# Brake.net
KiCad netlist of a schematic drawn in EAGLE
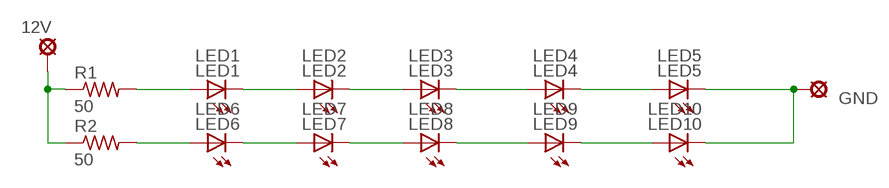
[diagram p0: schematic, sheet 1]

(export (version "E")
  (design (tool "Eeschema 10.0.6"))
  (components
    (comp (ref "12V")
      (value "LSP13")
      (footprint "eagle-import:LSP13")
      (libsource (lib "eagle-import") (part "LSP13"))
    )
    (comp (ref "GND")
      (value "LSP13")
      (footprint "eagle-import:LSP13")
      (libsource (lib "eagle-import") (part "LSP13"))
    )
    (comp (ref "LED1")
      (value "LED1")
      (footprint "eagle-import:CP41B")
      (libsource (lib "eagle-import") (part "LED-2AC-CP41B-WES"))
    )
    (comp (ref "LED2")
      (value "LED2")
      (footprint "eagle-import:CP41B")
      (libsource (lib "eagle-import") (part "LED-2AC-CP41B-WES"))
    )
    (comp (ref "LED3")
      (value "LED3")
      (footprint "eagle-import:CP41B")
      (libsource (lib "eagle-import") (part "LED-2AC-CP41B-WES"))
    )
    (comp (ref "LED4")
      (value "LED4")
      (footprint "eagle-import:CP41B")
      (libsource (lib "eagle-import") (part "LED-2AC-CP41B-WES"))
    )
    (comp (ref "LED5")
      (value "LED5")
      (footprint "eagle-import:CP41B")
      (libsource (lib "eagle-import") (part "LED-2AC-CP41B-WES"))
    )
    (comp (ref "LED6")
      (value "LED6")
      (footprint "eagle-import:CP41B")
      (libsource (lib "eagle-import") (part "LED-2AC-CP41B-WES"))
    )
    (comp (ref "LED7")
      (value "LED7")
      (footprint "eagle-import:CP41B")
      (libsource (lib "eagle-import") (part "LED-2AC-CP41B-WES"))
    )
    (comp (ref "LED8")
      (value "LED8")
      (footprint "eagle-import:CP41B")
      (libsource (lib "eagle-import") (part "LED-2AC-CP41B-WES"))
    )
    (comp (ref "LED9")
      (value "LED9")
      (footprint "eagle-import:CP41B")
      (libsource (lib "eagle-import") (part "LED-2AC-CP41B-WES"))
    )
    (comp (ref "LED10")
      (value "LED10")
      (footprint "eagle-import:CP41B")
      (libsource (lib "eagle-import") (part "LED-2AC-CP41B-WES"))
    )
    (comp (ref "R1")
      (value "50")
      (footprint "eagle-import:R1206")
      (libsource (lib "eagle-import") (part "R-US_R1206"))
    )
    (comp (ref "R2")
      (value "50")
      (footprint "eagle-import:R1206")
      (libsource (lib "eagle-import") (part "R-US_R1206"))
    )
  )
  (nets
    (net (code "1") (name "Net-(12V-PadMP)") (class "Default")
      (node (ref "12V") (pin "MP") (pinfunction "MP_MP") (pintype "passive"))
      (node (ref "R1") (pin "1") (pinfunction "1_1") (pintype "passive"))
      (node (ref "R2") (pin "1") (pinfunction "1_1") (pintype "passive"))
    )
    (net (code "2") (name "Net-(GND-PadMP)") (class "Default")
      (node (ref "GND") (pin "MP") (pinfunction "MP_MP") (pintype "passive"))
      (node (ref "LED10") (pin "1") (pinfunction "C_1") (pintype "passive"))
      (node (ref "LED10") (pin "4") (pinfunction "C_4") (pintype "passive"))
      (node (ref "LED5") (pin "1") (pinfunction "C_1") (pintype "passive"))
      (node (ref "LED5") (pin "4") (pinfunction "C_4") (pintype "passive"))
    )
    (net (code "3") (name "Net-(LED1-A-Pad2)") (class "Default")
      (node (ref "LED1") (pin "2") (pinfunction "A_2") (pintype "passive"))
      (node (ref "LED1") (pin "3") (pinfunction "A_3") (pintype "passive"))
      (node (ref "R1") (pin "2") (pinfunction "2_2") (pintype "passive"))
    )
    (net (code "4") (name "Net-(LED1-C-Pad1)") (class "Default")
      (node (ref "LED1") (pin "1") (pinfunction "C_1") (pintype "passive"))
      (node (ref "LED1") (pin "4") (pinfunction "C_4") (pintype "passive"))
      (node (ref "LED2") (pin "2") (pinfunction "A_2") (pintype "passive"))
      (node (ref "LED2") (pin "3") (pinfunction "A_3") (pintype "passive"))
    )
    (net (code "5") (name "Net-(LED2-C-Pad1)") (class "Default")
      (node (ref "LED2") (pin "1") (pinfunction "C_1") (pintype "passive"))
      (node (ref "LED2") (pin "4") (pinfunction "C_4") (pintype "passive"))
      (node (ref "LED3") (pin "2") (pinfunction "A_2") (pintype "passive"))
      (node (ref "LED3") (pin "3") (pinfunction "A_3") (pintype "passive"))
    )
    (net (code "6") (name "Net-(LED3-C-Pad1)") (class "Default")
      (node (ref "LED3") (pin "1") (pinfunction "C_1") (pintype "passive"))
      (node (ref "LED3") (pin "4") (pinfunction "C_4") (pintype "passive"))
      (node (ref "LED4") (pin "2") (pinfunction "A_2") (pintype "passive"))
      (node (ref "LED4") (pin "3") (pinfunction "A_3") (pintype "passive"))
    )
    (net (code "7") (name "Net-(LED4-C-Pad1)") (class "Default")
      (node (ref "LED4") (pin "1") (pinfunction "C_1") (pintype "passive"))
      (node (ref "LED4") (pin "4") (pinfunction "C_4") (pintype "passive"))
      (node (ref "LED5") (pin "2") (pinfunction "A_2") (pintype "passive"))
      (node (ref "LED5") (pin "3") (pinfunction "A_3") (pintype "passive"))
    )
    (net (code "8") (name "Net-(LED6-A-Pad2)") (class "Default")
      (node (ref "LED6") (pin "2") (pinfunction "A_2") (pintype "passive"))
      (node (ref "LED6") (pin "3") (pinfunction "A_3") (pintype "passive"))
      (node (ref "R2") (pin "2") (pinfunction "2_2") (pintype "passive"))
    )
    (net (code "9") (name "Net-(LED6-C-Pad1)") (class "Default")
      (node (ref "LED6") (pin "1") (pinfunction "C_1") (pintype "passive"))
      (node (ref "LED6") (pin "4") (pinfunction "C_4") (pintype "passive"))
      (node (ref "LED7") (pin "2") (pinfunction "A_2") (pintype "passive"))
      (node (ref "LED7") (pin "3") (pinfunction "A_3") (pintype "passive"))
    )
    (net (code "10") (name "Net-(LED7-C-Pad1)") (class "Default")
      (node (ref "LED7") (pin "1") (pinfunction "C_1") (pintype "passive"))
      (node (ref "LED7") (pin "4") (pinfunction "C_4") (pintype "passive"))
      (node (ref "LED8") (pin "2") (pinfunction "A_2") (pintype "passive"))
      (node (ref "LED8") (pin "3") (pinfunction "A_3") (pintype "passive"))
    )
    (net (code "11") (name "Net-(LED8-C-Pad1)") (class "Default")
      (node (ref "LED8") (pin "1") (pinfunction "C_1") (pintype "passive"))
      (node (ref "LED8") (pin "4") (pinfunction "C_4") (pintype "passive"))
      (node (ref "LED9") (pin "2") (pinfunction "A_2") (pintype "passive"))
      (node (ref "LED9") (pin "3") (pinfunction "A_3") (pintype "passive"))
    )
    (net (code "12") (name "Net-(LED10-A-Pad2)") (class "Default")
      (node (ref "LED10") (pin "2") (pinfunction "A_2") (pintype "passive"))
      (node (ref "LED10") (pin "3") (pinfunction "A_3") (pintype "passive"))
      (node (ref "LED9") (pin "1") (pinfunction "C_1") (pintype "passive"))
      (node (ref "LED9") (pin "4") (pinfunction "C_4") (pintype "passive"))
    )
  )
)
